# Conn_A.net
KiCad netlist of a schematic drawn in Altium Designer
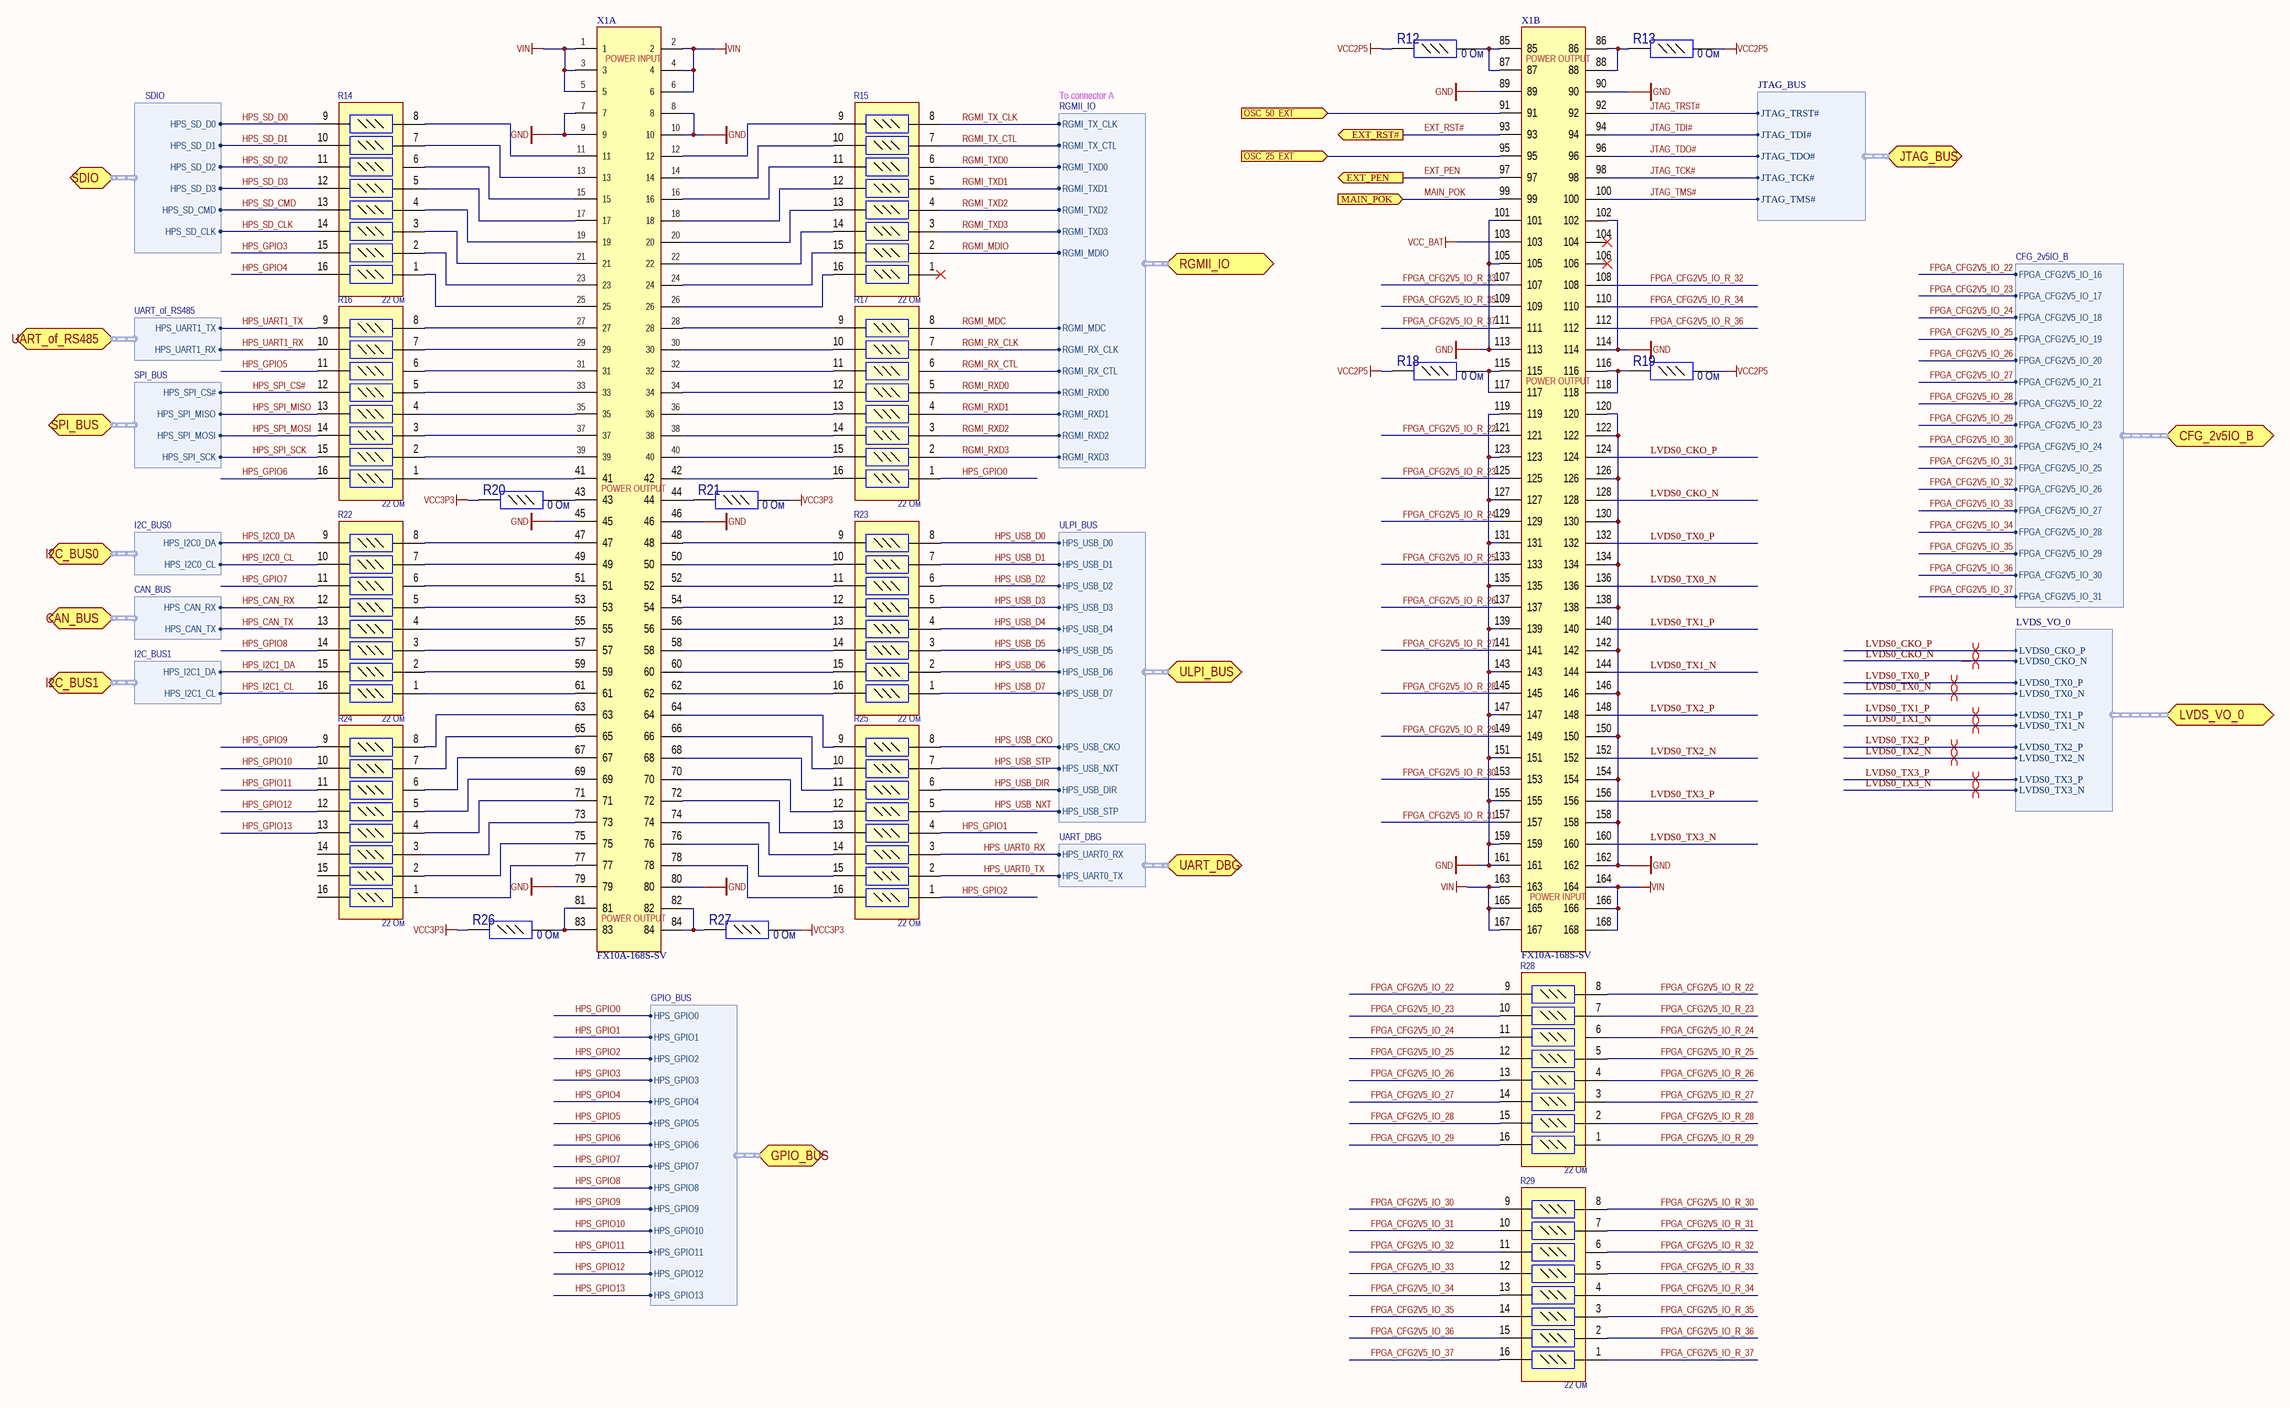
[diagram p0: Conn_A.SchDoc]

(export (version "E")
  (design (tool "Eeschema 10.0.6"))
  (components
    (comp (ref "R12")
      (value "0 Ом")
      (footprint "CR0603")
      (description "Чип резистор")
      (fields (field (name "Comment") "CR0603-0 Ом-±5%"))
      (libsource (lib "Резисторы") (part "CR0603-#-±5%"))
    )
    (comp (ref "R13")
      (value "0 Ом")
      (footprint "CR0603")
      (description "Чип резистор")
      (fields (field (name "Comment") "CR0603-0 Ом-±5%"))
      (libsource (lib "Резисторы") (part "CR0603-#-±5%"))
    )
    (comp (ref "R14")
      (value "22 Ом")
      (footprint "CAT16-J8")
      (description "Набор чип резисторов")
      (fields (field (name "Comment") "YC248-JR-07-22 Ом"))
      (libsource (lib "SD_IC") (part "YC248-JR-07-#"))
    )
    (comp (ref "R15")
      (value "22 Ом")
      (footprint "CAT16-J8")
      (description "Набор чип резисторов")
      (fields (field (name "Comment") "YC248-JR-07-22 Ом"))
      (libsource (lib "SD_IC") (part "YC248-JR-07-#"))
    )
    (comp (ref "R16")
      (value "22 Ом")
      (footprint "CAT16-J8")
      (description "Набор чип резисторов")
      (fields (field (name "Comment") "YC248-JR-07-22 Ом"))
      (libsource (lib "SD_IC") (part "YC248-JR-07-#"))
    )
    (comp (ref "R17")
      (value "22 Ом")
      (footprint "CAT16-J8")
      (description "Набор чип резисторов")
      (fields (field (name "Comment") "YC248-JR-07-22 Ом"))
      (libsource (lib "SD_IC") (part "YC248-JR-07-#"))
    )
    (comp (ref "R18")
      (value "0 Ом")
      (footprint "CR0603")
      (description "Чип резистор")
      (fields (field (name "Comment") "CR0603-0 Ом-±5%"))
      (libsource (lib "Резисторы") (part "CR0603-#-±5%"))
    )
    (comp (ref "R19")
      (value "0 Ом")
      (footprint "CR0603")
      (description "Чип резистор")
      (fields (field (name "Comment") "CR0603-0 Ом-±5%"))
      (libsource (lib "Резисторы") (part "CR0603-#-±5%"))
    )
    (comp (ref "R20")
      (value "0 Ом")
      (footprint "CR0603")
      (description "Чип резистор")
      (fields (field (name "Comment") "CR0603-0 Ом-±5%"))
      (libsource (lib "Резисторы") (part "CR0603-#-±5%"))
    )
    (comp (ref "R21")
      (value "0 Ом")
      (footprint "CR0603")
      (description "Чип резистор")
      (fields (field (name "Comment") "CR0603-0 Ом-±5%"))
      (libsource (lib "Резисторы") (part "CR0603-#-±5%"))
    )
    (comp (ref "R22")
      (value "22 Ом")
      (footprint "CAT16-J8")
      (description "Набор чип резисторов")
      (fields (field (name "Comment") "YC248-JR-07-22 Ом"))
      (libsource (lib "SD_IC") (part "YC248-JR-07-#"))
    )
    (comp (ref "R23")
      (value "22 Ом")
      (footprint "CAT16-J8")
      (description "Набор чип резисторов")
      (fields (field (name "Comment") "YC248-JR-07-22 Ом"))
      (libsource (lib "SD_IC") (part "YC248-JR-07-#"))
    )
    (comp (ref "R24")
      (value "22 Ом")
      (footprint "CAT16-J8")
      (description "Набор чип резисторов")
      (fields (field (name "Comment") "YC248-JR-07-22 Ом"))
      (libsource (lib "SD_IC") (part "YC248-JR-07-#"))
    )
    (comp (ref "R25")
      (value "22 Ом")
      (footprint "CAT16-J8")
      (description "Набор чип резисторов")
      (fields (field (name "Comment") "YC248-JR-07-22 Ом"))
      (libsource (lib "SD_IC") (part "YC248-JR-07-#"))
    )
    (comp (ref "R26")
      (value "0 Ом")
      (footprint "CR0603")
      (description "Чип резистор")
      (fields (field (name "Comment") "CR0603-0 Ом-±5%"))
      (libsource (lib "Резисторы") (part "CR0603-#-±5%"))
    )
    (comp (ref "R27")
      (value "0 Ом")
      (footprint "CR0603")
      (description "Чип резистор")
      (fields (field (name "Comment") "CR0603-0 Ом-±5%"))
      (libsource (lib "Резисторы") (part "CR0603-#-±5%"))
    )
    (comp (ref "R28")
      (value "22 Ом")
      (footprint "CAT16-J8")
      (description "Набор чип резисторов")
      (fields (field (name "Comment") "YC248-JR-07-22 Ом"))
      (libsource (lib "SD_IC") (part "YC248-JR-07-#"))
    )
    (comp (ref "R29")
      (value "22 Ом")
      (footprint "CAT16-J8")
      (description "Набор чип резисторов")
      (fields (field (name "Comment") "YC248-JR-07-22 Ом"))
      (libsource (lib "SD_IC") (part "YC248-JR-07-#"))
    )
    (comp (ref "X1")
      (value "FX10A-168S-SV")
      (footprint "FX10A-168S-SV")
      (libsource (lib "SD_IC") (part "FX10A-168S-SV"))
    )
  )
  (nets
    (net (code "14") (name "/EXT_PEN") (class "Default")
      (node (ref "X1") (pin "97") (pinfunction "97_97") (pintype "passive"))
    )
    (net (code "15") (name "/EXT_RST#") (class "Default")
      (node (ref "X1") (pin "93") (pinfunction "93_93") (pintype "passive"))
    )
    (net (code "16") (name "/FPGA_CFG2V5_IO_22") (class "Default")
      (node (ref "R28") (pin "9") (pintype "passive"))
    )
    (net (code "17") (name "/FPGA_CFG2V5_IO_23") (class "Default")
      (node (ref "R28") (pin "10") (pintype "passive"))
    )
    (net (code "18") (name "/FPGA_CFG2V5_IO_24") (class "Default")
      (node (ref "R28") (pin "11") (pintype "passive"))
    )
    (net (code "19") (name "/FPGA_CFG2V5_IO_25") (class "Default")
      (node (ref "R28") (pin "12") (pintype "passive"))
    )
    (net (code "20") (name "/FPGA_CFG2V5_IO_26") (class "Default")
      (node (ref "R28") (pin "13") (pintype "passive"))
    )
    (net (code "21") (name "/FPGA_CFG2V5_IO_27") (class "Default")
      (node (ref "R28") (pin "14") (pintype "passive"))
    )
    (net (code "22") (name "/FPGA_CFG2V5_IO_28") (class "Default")
      (node (ref "R28") (pin "15") (pintype "passive"))
    )
    (net (code "23") (name "/FPGA_CFG2V5_IO_29") (class "Default")
      (node (ref "R28") (pin "16") (pintype "passive"))
    )
    (net (code "24") (name "/FPGA_CFG2V5_IO_30") (class "Default")
      (node (ref "R29") (pin "9") (pintype "passive"))
    )
    (net (code "25") (name "/FPGA_CFG2V5_IO_31") (class "Default")
      (node (ref "R29") (pin "10") (pintype "passive"))
    )
    (net (code "26") (name "/FPGA_CFG2V5_IO_32") (class "Default")
      (node (ref "R29") (pin "11") (pintype "passive"))
    )
    (net (code "27") (name "/FPGA_CFG2V5_IO_33") (class "Default")
      (node (ref "R29") (pin "12") (pintype "passive"))
    )
    (net (code "28") (name "/FPGA_CFG2V5_IO_34") (class "Default")
      (node (ref "R29") (pin "13") (pintype "passive"))
    )
    (net (code "29") (name "/FPGA_CFG2V5_IO_35") (class "Default")
      (node (ref "R29") (pin "14") (pintype "passive"))
    )
    (net (code "30") (name "/FPGA_CFG2V5_IO_36") (class "Default")
      (node (ref "R29") (pin "15") (pintype "passive"))
    )
    (net (code "31") (name "/FPGA_CFG2V5_IO_37") (class "Default")
      (node (ref "R29") (pin "16") (pintype "passive"))
    )
    (net (code "32") (name "/FPGA_CFG2V5_IO_R_22") (class "Default")
      (node (ref "R28") (pin "8") (pintype "passive"))
      (node (ref "X1") (pin "121") (pinfunction "121_121") (pintype "passive"))
    )
    (net (code "33") (name "/FPGA_CFG2V5_IO_R_23") (class "Default")
      (node (ref "R28") (pin "7") (pintype "passive"))
      (node (ref "X1") (pin "125") (pinfunction "125_125") (pintype "passive"))
    )
    (net (code "34") (name "/FPGA_CFG2V5_IO_R_24") (class "Default")
      (node (ref "R28") (pin "6") (pintype "passive"))
      (node (ref "X1") (pin "129") (pinfunction "129_129") (pintype "passive"))
    )
    (net (code "35") (name "/FPGA_CFG2V5_IO_R_25") (class "Default")
      (node (ref "R28") (pin "5") (pintype "passive"))
      (node (ref "X1") (pin "133") (pinfunction "133_133") (pintype "passive"))
    )
    (net (code "36") (name "/FPGA_CFG2V5_IO_R_26") (class "Default")
      (node (ref "R28") (pin "4") (pintype "passive"))
      (node (ref "X1") (pin "137") (pinfunction "137_137") (pintype "passive"))
    )
    (net (code "37") (name "/FPGA_CFG2V5_IO_R_27") (class "Default")
      (node (ref "R28") (pin "3") (pintype "passive"))
      (node (ref "X1") (pin "141") (pinfunction "141_141") (pintype "passive"))
    )
    (net (code "38") (name "/FPGA_CFG2V5_IO_R_28") (class "Default")
      (node (ref "R28") (pin "2") (pintype "passive"))
      (node (ref "X1") (pin "145") (pinfunction "145_145") (pintype "passive"))
    )
    (net (code "39") (name "/FPGA_CFG2V5_IO_R_29") (class "Default")
      (node (ref "R28") (pin "1") (pintype "passive"))
      (node (ref "X1") (pin "149") (pinfunction "149_149") (pintype "passive"))
    )
    (net (code "40") (name "/FPGA_CFG2V5_IO_R_30") (class "Default")
      (node (ref "R29") (pin "8") (pintype "passive"))
      (node (ref "X1") (pin "153") (pinfunction "153_153") (pintype "passive"))
    )
    (net (code "41") (name "/FPGA_CFG2V5_IO_R_31") (class "Default")
      (node (ref "R29") (pin "7") (pintype "passive"))
      (node (ref "X1") (pin "157") (pinfunction "157_157") (pintype "passive"))
    )
    (net (code "42") (name "/FPGA_CFG2V5_IO_R_32") (class "Default")
      (node (ref "R29") (pin "6") (pintype "passive"))
      (node (ref "X1") (pin "108") (pinfunction "108_108") (pintype "passive"))
    )
    (net (code "43") (name "/FPGA_CFG2V5_IO_R_33") (class "Default")
      (node (ref "R29") (pin "5") (pintype "passive"))
      (node (ref "X1") (pin "107") (pinfunction "107_107") (pintype "passive"))
    )
    (net (code "44") (name "/FPGA_CFG2V5_IO_R_34") (class "Default")
      (node (ref "R29") (pin "4") (pintype "passive"))
      (node (ref "X1") (pin "110") (pinfunction "110_110") (pintype "passive"))
    )
    (net (code "45") (name "/FPGA_CFG2V5_IO_R_35") (class "Default")
      (node (ref "R29") (pin "3") (pintype "passive"))
      (node (ref "X1") (pin "109") (pinfunction "109_109") (pintype "passive"))
    )
    (net (code "46") (name "/FPGA_CFG2V5_IO_R_36") (class "Default")
      (node (ref "R29") (pin "2") (pintype "passive"))
      (node (ref "X1") (pin "112") (pinfunction "112_112") (pintype "passive"))
    )
    (net (code "47") (name "/FPGA_CFG2V5_IO_R_37") (class "Default")
      (node (ref "R29") (pin "1") (pintype "passive"))
      (node (ref "X1") (pin "111") (pinfunction "111_111") (pintype "passive"))
    )
    (net (code "48") (name "/HPS_CAN_RX") (class "Default") (node (ref "R22") (pin "12") (pintype "passive")))
    (net (code "49") (name "/HPS_CAN_TX") (class "Default") (node (ref "R22") (pin "13") (pintype "passive")))
    (net (code "50") (name "/HPS_GPIO0") (class "Default") (node (ref "R17") (pin "1") (pintype "passive")))
    (net (code "51") (name "/HPS_GPIO1") (class "Default") (node (ref "R25") (pin "4") (pintype "passive")))
    (net (code "52") (name "/HPS_GPIO2") (class "Default") (node (ref "R25") (pin "1") (pintype "passive")))
    (net (code "53") (name "/HPS_GPIO3") (class "Default") (node (ref "R14") (pin "15") (pintype "passive")))
    (net (code "54") (name "/HPS_GPIO4") (class "Default") (node (ref "R14") (pin "16") (pintype "passive")))
    (net (code "55") (name "/HPS_GPIO5") (class "Default") (node (ref "R16") (pin "11") (pintype "passive")))
    (net (code "56") (name "/HPS_GPIO6") (class "Default") (node (ref "R16") (pin "16") (pintype "passive")))
    (net (code "57") (name "/HPS_GPIO7") (class "Default") (node (ref "R22") (pin "11") (pintype "passive")))
    (net (code "58") (name "/HPS_GPIO8") (class "Default") (node (ref "R22") (pin "14") (pintype "passive")))
    (net (code "59") (name "/HPS_GPIO9") (class "Default") (node (ref "R24") (pin "9") (pintype "passive")))
    (net (code "60") (name "/HPS_GPIO10") (class "Default") (node (ref "R24") (pin "10") (pintype "passive")))
    (net (code "61") (name "/HPS_GPIO11") (class "Default") (node (ref "R24") (pin "11") (pintype "passive")))
    (net (code "62") (name "/HPS_GPIO12") (class "Default") (node (ref "R24") (pin "12") (pintype "passive")))
    (net (code "63") (name "/HPS_GPIO13") (class "Default") (node (ref "R24") (pin "13") (pintype "passive")))
    (net (code "64") (name "/HPS_I2C0_CL") (class "Default")
      (node (ref "R22") (pin "10") (pintype "passive"))
    )
    (net (code "65") (name "/HPS_I2C0_DA") (class "Default") (node (ref "R22") (pin "9") (pintype "passive")))
    (net (code "66") (name "/HPS_I2C1_CL") (class "Default")
      (node (ref "R22") (pin "16") (pintype "passive"))
    )
    (net (code "67") (name "/HPS_I2C1_DA") (class "Default")
      (node (ref "R22") (pin "15") (pintype "passive"))
    )
    (net (code "68") (name "/HPS_SD_CLK") (class "Default") (node (ref "R14") (pin "14") (pintype "passive")))
    (net (code "69") (name "/HPS_SD_CMD") (class "Default") (node (ref "R14") (pin "13") (pintype "passive")))
    (net (code "70") (name "/HPS_SD_D0") (class "Default") (node (ref "R14") (pin "9") (pintype "passive")))
    (net (code "71") (name "/HPS_SD_D1") (class "Default") (node (ref "R14") (pin "10") (pintype "passive")))
    (net (code "72") (name "/HPS_SD_D2") (class "Default") (node (ref "R14") (pin "11") (pintype "passive")))
    (net (code "73") (name "/HPS_SD_D3") (class "Default") (node (ref "R14") (pin "12") (pintype "passive")))
    (net (code "74") (name "/HPS_SPI_CS#") (class "Default")
      (node (ref "R16") (pin "12") (pintype "passive"))
    )
    (net (code "75") (name "/HPS_SPI_MISO") (class "Default")
      (node (ref "R16") (pin "13") (pintype "passive"))
    )
    (net (code "76") (name "/HPS_SPI_MOSI") (class "Default")
      (node (ref "R16") (pin "14") (pintype "passive"))
    )
    (net (code "77") (name "/HPS_SPI_SCK") (class "Default")
      (node (ref "R16") (pin "15") (pintype "passive"))
    )
    (net (code "78") (name "/HPS_UART0_RX") (class "Default")
      (node (ref "R25") (pin "3") (pintype "passive"))
    )
    (net (code "79") (name "/HPS_UART0_TX") (class "Default")
      (node (ref "R25") (pin "2") (pintype "passive"))
    )
    (net (code "80") (name "/HPS_UART1_RX") (class "Default")
      (node (ref "R16") (pin "10") (pintype "passive"))
    )
    (net (code "81") (name "/HPS_UART1_TX") (class "Default")
      (node (ref "R16") (pin "9") (pintype "passive"))
    )
    (net (code "82") (name "/HPS_USB_CKO") (class "Default") (node (ref "R25") (pin "8") (pintype "passive")))
    (net (code "83") (name "/HPS_USB_D0") (class "Default") (node (ref "R23") (pin "8") (pintype "passive")))
    (net (code "84") (name "/HPS_USB_D1") (class "Default") (node (ref "R23") (pin "7") (pintype "passive")))
    (net (code "85") (name "/HPS_USB_D2") (class "Default") (node (ref "R23") (pin "6") (pintype "passive")))
    (net (code "86") (name "/HPS_USB_D3") (class "Default") (node (ref "R23") (pin "5") (pintype "passive")))
    (net (code "87") (name "/HPS_USB_D4") (class "Default") (node (ref "R23") (pin "4") (pintype "passive")))
    (net (code "88") (name "/HPS_USB_D5") (class "Default") (node (ref "R23") (pin "3") (pintype "passive")))
    (net (code "89") (name "/HPS_USB_D6") (class "Default") (node (ref "R23") (pin "2") (pintype "passive")))
    (net (code "90") (name "/HPS_USB_D7") (class "Default") (node (ref "R23") (pin "1") (pintype "passive")))
    (net (code "91") (name "/HPS_USB_DIR") (class "Default") (node (ref "R25") (pin "6") (pintype "passive")))
    (net (code "92") (name "/HPS_USB_NXT") (class "Default") (node (ref "R25") (pin "5") (pintype "passive")))
    (net (code "93") (name "/HPS_USB_STP") (class "Default") (node (ref "R25") (pin "7") (pintype "passive")))
    (net (code "94") (name "/JTAG_TCK#") (class "Default")
      (node (ref "X1") (pin "98") (pinfunction "98_98") (pintype "passive"))
    )
    (net (code "95") (name "/JTAG_TDI#") (class "Default")
      (node (ref "X1") (pin "94") (pinfunction "94_94") (pintype "passive"))
    )
    (net (code "96") (name "/JTAG_TDO#") (class "Default")
      (node (ref "X1") (pin "96") (pinfunction "96_96") (pintype "passive"))
    )
    (net (code "97") (name "/JTAG_TMS#") (class "Default")
      (node (ref "X1") (pin "100") (pinfunction "100_100") (pintype "passive"))
    )
    (net (code "98") (name "/JTAG_TRST#") (class "Default")
      (node (ref "X1") (pin "92") (pinfunction "92_92") (pintype "passive"))
    )
    (net (code "99") (name "/LVDS0_CKO_N") (class "Default")
      (node (ref "X1") (pin "128") (pinfunction "128_128") (pintype "passive"))
    )
    (net (code "100") (name "/LVDS0_CKO_P") (class "Default")
      (node (ref "X1") (pin "124") (pinfunction "124_124") (pintype "passive"))
    )
    (net (code "101") (name "/LVDS0_TX0_N") (class "Default")
      (node (ref "X1") (pin "136") (pinfunction "136_136") (pintype "passive"))
    )
    (net (code "102") (name "/LVDS0_TX0_P") (class "Default")
      (node (ref "X1") (pin "132") (pinfunction "132_132") (pintype "passive"))
    )
    (net (code "103") (name "/LVDS0_TX1_N") (class "Default")
      (node (ref "X1") (pin "144") (pinfunction "144_144") (pintype "passive"))
    )
    (net (code "104") (name "/LVDS0_TX1_P") (class "Default")
      (node (ref "X1") (pin "140") (pinfunction "140_140") (pintype "passive"))
    )
    (net (code "105") (name "/LVDS0_TX2_N") (class "Default")
      (node (ref "X1") (pin "152") (pinfunction "152_152") (pintype "passive"))
    )
    (net (code "106") (name "/LVDS0_TX2_P") (class "Default")
      (node (ref "X1") (pin "148") (pinfunction "148_148") (pintype "passive"))
    )
    (net (code "107") (name "/LVDS0_TX3_N") (class "Default")
      (node (ref "X1") (pin "160") (pinfunction "160_160") (pintype "passive"))
    )
    (net (code "108") (name "/LVDS0_TX3_P") (class "Default")
      (node (ref "X1") (pin "156") (pinfunction "156_156") (pintype "passive"))
    )
    (net (code "109") (name "/MAIN_POK") (class "Default")
      (node (ref "X1") (pin "99") (pinfunction "99_99") (pintype "passive"))
    )
    (net (code "110") (name "/OSC_25_EXT") (class "Default")
      (node (ref "X1") (pin "95") (pinfunction "95_95") (pintype "passive"))
    )
    (net (code "111") (name "/OSC_50_EXT") (class "Default")
      (node (ref "X1") (pin "91") (pinfunction "91_91") (pintype "passive"))
    )
    (net (code "112") (name "/RGMI_MDC") (class "Default") (node (ref "R17") (pin "8") (pintype "passive")))
    (net (code "113") (name "/RGMI_MDIO") (class "Default") (node (ref "R15") (pin "2") (pintype "passive")))
    (net (code "114") (name "/RGMI_RXD0") (class "Default") (node (ref "R17") (pin "5") (pintype "passive")))
    (net (code "115") (name "/RGMI_RXD1") (class "Default") (node (ref "R17") (pin "4") (pintype "passive")))
    (net (code "116") (name "/RGMI_RXD2") (class "Default") (node (ref "R17") (pin "3") (pintype "passive")))
    (net (code "117") (name "/RGMI_RXD3") (class "Default") (node (ref "R17") (pin "2") (pintype "passive")))
    (net (code "118") (name "/RGMI_RX_CLK") (class "Default")
      (node (ref "R17") (pin "7") (pintype "passive"))
    )
    (net (code "119") (name "/RGMI_RX_CTL") (class "Default")
      (node (ref "R17") (pin "6") (pintype "passive"))
    )
    (net (code "120") (name "/RGMI_TXD0") (class "Default") (node (ref "R15") (pin "6") (pintype "passive")))
    (net (code "121") (name "/RGMI_TXD1") (class "Default") (node (ref "R15") (pin "5") (pintype "passive")))
    (net (code "122") (name "/RGMI_TXD2") (class "Default") (node (ref "R15") (pin "4") (pintype "passive")))
    (net (code "123") (name "/RGMI_TXD3") (class "Default") (node (ref "R15") (pin "3") (pintype "passive")))
    (net (code "124") (name "/RGMI_TX_CLK") (class "Default")
      (node (ref "R15") (pin "8") (pintype "passive"))
    )
    (net (code "125") (name "/RGMI_TX_CTL") (class "Default")
      (node (ref "R15") (pin "7") (pintype "passive"))
    )
    (net (code "139") (name "GND") (class "Default")
      (node (ref "X1") (pin "10") (pinfunction "10_10") (pintype "passive"))
      (node (ref "X1") (pin "101") (pinfunction "101_101") (pintype "passive"))
      (node (ref "X1") (pin "102") (pinfunction "102_102") (pintype "passive"))
      (node (ref "X1") (pin "105") (pinfunction "105_105") (pintype "passive"))
      (node (ref "X1") (pin "113") (pinfunction "113_113") (pintype "passive"))
      (node (ref "X1") (pin "114") (pinfunction "114_114") (pintype "passive"))
      (node (ref "X1") (pin "119") (pinfunction "119_119") (pintype "passive"))
      (node (ref "X1") (pin "120") (pinfunction "120_120") (pintype "passive"))
      (node (ref "X1") (pin "122") (pinfunction "122_122") (pintype "passive"))
      (node (ref "X1") (pin "123") (pinfunction "123_123") (pintype "passive"))
      (node (ref "X1") (pin "126") (pinfunction "126_126") (pintype "passive"))
      (node (ref "X1") (pin "127") (pinfunction "127_127") (pintype "passive"))
      (node (ref "X1") (pin "130") (pinfunction "130_130") (pintype "passive"))
      (node (ref "X1") (pin "131") (pinfunction "131_131") (pintype "passive"))
      (node (ref "X1") (pin "134") (pinfunction "134_134") (pintype "passive"))
      (node (ref "X1") (pin "135") (pinfunction "135_135") (pintype "passive"))
      (node (ref "X1") (pin "138") (pinfunction "138_138") (pintype "passive"))
      (node (ref "X1") (pin "139") (pinfunction "139_139") (pintype "passive"))
      (node (ref "X1") (pin "142") (pinfunction "142_142") (pintype "passive"))
      (node (ref "X1") (pin "143") (pinfunction "143_143") (pintype "passive"))
      (node (ref "X1") (pin "146") (pinfunction "146_146") (pintype "passive"))
      (node (ref "X1") (pin "147") (pinfunction "147_147") (pintype "passive"))
      (node (ref "X1") (pin "150") (pinfunction "150_150") (pintype "passive"))
      (node (ref "X1") (pin "151") (pinfunction "151_151") (pintype "passive"))
      (node (ref "X1") (pin "154") (pinfunction "154_154") (pintype "passive"))
      (node (ref "X1") (pin "155") (pinfunction "155_155") (pintype "passive"))
      (node (ref "X1") (pin "158") (pinfunction "158_158") (pintype "passive"))
      (node (ref "X1") (pin "159") (pinfunction "159_159") (pintype "passive"))
      (node (ref "X1") (pin "161") (pinfunction "161_161") (pintype "passive"))
      (node (ref "X1") (pin "162") (pinfunction "162_162") (pintype "passive"))
      (node (ref "X1") (pin "45") (pinfunction "45_45") (pintype "passive"))
      (node (ref "X1") (pin "46") (pinfunction "46_46") (pintype "passive"))
      (node (ref "X1") (pin "7") (pinfunction "7_7") (pintype "passive"))
      (node (ref "X1") (pin "79") (pinfunction "79_79") (pintype "passive"))
      (node (ref "X1") (pin "8") (pinfunction "8_8") (pintype "passive"))
      (node (ref "X1") (pin "80") (pinfunction "80_80") (pintype "passive"))
      (node (ref "X1") (pin "89") (pinfunction "89_89") (pintype "passive"))
      (node (ref "X1") (pin "9") (pinfunction "9_9") (pintype "passive"))
      (node (ref "X1") (pin "90") (pinfunction "90_90") (pintype "passive"))
    )
    (net (code "140") (name "Net-(R12--)") (class "Default")
      (node (ref "R12") (pin "2") (pinfunction "-_2") (pintype "passive"))
      (node (ref "X1") (pin "85") (pinfunction "85_85") (pintype "passive"))
      (node (ref "X1") (pin "87") (pinfunction "87_87") (pintype "passive"))
    )
    (net (code "141") (name "Net-(R13-+)") (class "Default")
      (node (ref "R13") (pin "1") (pinfunction "+_1") (pintype "passive"))
      (node (ref "X1") (pin "86") (pinfunction "86_86") (pintype "passive"))
      (node (ref "X1") (pin "88") (pinfunction "88_88") (pintype "passive"))
    )
    (net (code "142") (name "Net-(R14-Pad1)") (class "Default")
      (node (ref "R14") (pin "1") (pintype "passive"))
      (node (ref "X1") (pin "25") (pinfunction "25_25") (pintype "passive"))
    )
    (net (code "143") (name "Net-(R14-Pad2)") (class "Default")
      (node (ref "R14") (pin "2") (pintype "passive"))
      (node (ref "X1") (pin "23") (pinfunction "23_23") (pintype "passive"))
    )
    (net (code "144") (name "Net-(R14-Pad3)") (class "Default")
      (node (ref "R14") (pin "3") (pintype "passive"))
      (node (ref "X1") (pin "21") (pinfunction "21_21") (pintype "passive"))
    )
    (net (code "145") (name "Net-(R14-Pad4)") (class "Default")
      (node (ref "R14") (pin "4") (pintype "passive"))
      (node (ref "X1") (pin "19") (pinfunction "19_19") (pintype "passive"))
    )
    (net (code "146") (name "Net-(R14-Pad5)") (class "Default")
      (node (ref "R14") (pin "5") (pintype "passive"))
      (node (ref "X1") (pin "17") (pinfunction "17_17") (pintype "passive"))
    )
    (net (code "147") (name "Net-(R14-Pad6)") (class "Default")
      (node (ref "R14") (pin "6") (pintype "passive"))
      (node (ref "X1") (pin "15") (pinfunction "15_15") (pintype "passive"))
    )
    (net (code "148") (name "Net-(R14-Pad7)") (class "Default")
      (node (ref "R14") (pin "7") (pintype "passive"))
      (node (ref "X1") (pin "13") (pinfunction "13_13") (pintype "passive"))
    )
    (net (code "149") (name "Net-(R14-Pad8)") (class "Default")
      (node (ref "R14") (pin "8") (pintype "passive"))
      (node (ref "X1") (pin "11") (pinfunction "11_11") (pintype "passive"))
    )
    (net (code "150") (name "Net-(R15-Pad9)") (class "Default")
      (node (ref "R15") (pin "9") (pintype "passive"))
      (node (ref "X1") (pin "12") (pinfunction "12_12") (pintype "passive"))
    )
    (net (code "151") (name "Net-(R15-Pad10)") (class "Default")
      (node (ref "R15") (pin "10") (pintype "passive"))
      (node (ref "X1") (pin "14") (pinfunction "14_14") (pintype "passive"))
    )
    (net (code "152") (name "Net-(R15-Pad11)") (class "Default")
      (node (ref "R15") (pin "11") (pintype "passive"))
      (node (ref "X1") (pin "16") (pinfunction "16_16") (pintype "passive"))
    )
    (net (code "153") (name "Net-(R15-Pad12)") (class "Default")
      (node (ref "R15") (pin "12") (pintype "passive"))
      (node (ref "X1") (pin "18") (pinfunction "18_18") (pintype "passive"))
    )
    (net (code "154") (name "Net-(R15-Pad13)") (class "Default")
      (node (ref "R15") (pin "13") (pintype "passive"))
      (node (ref "X1") (pin "20") (pinfunction "20_20") (pintype "passive"))
    )
    (net (code "155") (name "Net-(R15-Pad14)") (class "Default")
      (node (ref "R15") (pin "14") (pintype "passive"))
      (node (ref "X1") (pin "22") (pinfunction "22_22") (pintype "passive"))
    )
    (net (code "156") (name "Net-(R15-Pad15)") (class "Default")
      (node (ref "R15") (pin "15") (pintype "passive"))
      (node (ref "X1") (pin "24") (pinfunction "24_24") (pintype "passive"))
    )
    (net (code "157") (name "Net-(R15-Pad16)") (class "Default")
      (node (ref "R15") (pin "16") (pintype "passive"))
      (node (ref "X1") (pin "26") (pinfunction "26_26") (pintype "passive"))
    )
    (net (code "158") (name "Net-(R16-Pad1)") (class "Default")
      (node (ref "R16") (pin "1") (pintype "passive"))
      (node (ref "X1") (pin "41") (pinfunction "41_41") (pintype "passive"))
    )
    (net (code "159") (name "Net-(R16-Pad2)") (class "Default")
      (node (ref "R16") (pin "2") (pintype "passive"))
      (node (ref "X1") (pin "39") (pinfunction "39_39") (pintype "passive"))
    )
    (net (code "160") (name "Net-(R16-Pad3)") (class "Default")
      (node (ref "R16") (pin "3") (pintype "passive"))
      (node (ref "X1") (pin "37") (pinfunction "37_37") (pintype "passive"))
    )
    (net (code "161") (name "Net-(R16-Pad4)") (class "Default")
      (node (ref "R16") (pin "4") (pintype "passive"))
      (node (ref "X1") (pin "35") (pinfunction "35_35") (pintype "passive"))
    )
    (net (code "162") (name "Net-(R16-Pad5)") (class "Default")
      (node (ref "R16") (pin "5") (pintype "passive"))
      (node (ref "X1") (pin "33") (pinfunction "33_33") (pintype "passive"))
    )
    (net (code "163") (name "Net-(R16-Pad6)") (class "Default")
      (node (ref "R16") (pin "6") (pintype "passive"))
      (node (ref "X1") (pin "31") (pinfunction "31_31") (pintype "passive"))
    )
    (net (code "164") (name "Net-(R16-Pad7)") (class "Default")
      (node (ref "R16") (pin "7") (pintype "passive"))
      (node (ref "X1") (pin "29") (pinfunction "29_29") (pintype "passive"))
    )
    (net (code "165") (name "Net-(R16-Pad8)") (class "Default")
      (node (ref "R16") (pin "8") (pintype "passive"))
      (node (ref "X1") (pin "27") (pinfunction "27_27") (pintype "passive"))
    )
    (net (code "166") (name "Net-(R17-Pad9)") (class "Default")
      (node (ref "R17") (pin "9") (pintype "passive"))
      (node (ref "X1") (pin "28") (pinfunction "28_28") (pintype "passive"))
    )
    (net (code "167") (name "Net-(R17-Pad10)") (class "Default")
      (node (ref "R17") (pin "10") (pintype "passive"))
      (node (ref "X1") (pin "30") (pinfunction "30_30") (pintype "passive"))
    )
    (net (code "168") (name "Net-(R17-Pad11)") (class "Default")
      (node (ref "R17") (pin "11") (pintype "passive"))
      (node (ref "X1") (pin "32") (pinfunction "32_32") (pintype "passive"))
    )
    (net (code "169") (name "Net-(R17-Pad12)") (class "Default")
      (node (ref "R17") (pin "12") (pintype "passive"))
      (node (ref "X1") (pin "34") (pinfunction "34_34") (pintype "passive"))
    )
    (net (code "170") (name "Net-(R17-Pad13)") (class "Default")
      (node (ref "R17") (pin "13") (pintype "passive"))
      (node (ref "X1") (pin "36") (pinfunction "36_36") (pintype "passive"))
    )
    (net (code "171") (name "Net-(R17-Pad14)") (class "Default")
      (node (ref "R17") (pin "14") (pintype "passive"))
      (node (ref "X1") (pin "38") (pinfunction "38_38") (pintype "passive"))
    )
    (net (code "172") (name "Net-(R17-Pad15)") (class "Default")
      (node (ref "R17") (pin "15") (pintype "passive"))
      (node (ref "X1") (pin "40") (pinfunction "40_40") (pintype "passive"))
    )
    (net (code "173") (name "Net-(R17-Pad16)") (class "Default")
      (node (ref "R17") (pin "16") (pintype "passive"))
      (node (ref "X1") (pin "42") (pinfunction "42_42") (pintype "passive"))
    )
    (net (code "174") (name "Net-(R18--)") (class "Default")
      (node (ref "R18") (pin "2") (pinfunction "-_2") (pintype "passive"))
      (node (ref "X1") (pin "115") (pinfunction "115_115") (pintype "passive"))
      (node (ref "X1") (pin "117") (pinfunction "117_117") (pintype "passive"))
    )
    (net (code "175") (name "Net-(R19-+)") (class "Default")
      (node (ref "R19") (pin "1") (pinfunction "+_1") (pintype "passive"))
      (node (ref "X1") (pin "116") (pinfunction "116_116") (pintype "passive"))
      (node (ref "X1") (pin "118") (pinfunction "118_118") (pintype "passive"))
    )
    (net (code "176") (name "Net-(R20--)") (class "Default")
      (node (ref "R20") (pin "2") (pinfunction "-_2") (pintype "passive"))
      (node (ref "X1") (pin "43") (pinfunction "43_43") (pintype "passive"))
    )
    (net (code "177") (name "Net-(R21-+)") (class "Default")
      (node (ref "R21") (pin "1") (pinfunction "+_1") (pintype "passive"))
      (node (ref "X1") (pin "44") (pinfunction "44_44") (pintype "passive"))
    )
    (net (code "178") (name "Net-(R22-Pad1)") (class "Default")
      (node (ref "R22") (pin "1") (pintype "passive"))
      (node (ref "X1") (pin "61") (pinfunction "61_61") (pintype "passive"))
    )
    (net (code "179") (name "Net-(R22-Pad2)") (class "Default")
      (node (ref "R22") (pin "2") (pintype "passive"))
      (node (ref "X1") (pin "59") (pinfunction "59_59") (pintype "passive"))
    )
    (net (code "180") (name "Net-(R22-Pad3)") (class "Default")
      (node (ref "R22") (pin "3") (pintype "passive"))
      (node (ref "X1") (pin "57") (pinfunction "57_57") (pintype "passive"))
    )
    (net (code "181") (name "Net-(R22-Pad4)") (class "Default")
      (node (ref "R22") (pin "4") (pintype "passive"))
      (node (ref "X1") (pin "55") (pinfunction "55_55") (pintype "passive"))
    )
    (net (code "182") (name "Net-(R22-Pad5)") (class "Default")
      (node (ref "R22") (pin "5") (pintype "passive"))
      (node (ref "X1") (pin "53") (pinfunction "53_53") (pintype "passive"))
    )
    (net (code "183") (name "Net-(R22-Pad6)") (class "Default")
      (node (ref "R22") (pin "6") (pintype "passive"))
      (node (ref "X1") (pin "51") (pinfunction "51_51") (pintype "passive"))
    )
    (net (code "184") (name "Net-(R22-Pad7)") (class "Default")
      (node (ref "R22") (pin "7") (pintype "passive"))
      (node (ref "X1") (pin "49") (pinfunction "49_49") (pintype "passive"))
    )
    (net (code "185") (name "Net-(R22-Pad8)") (class "Default")
      (node (ref "R22") (pin "8") (pintype "passive"))
      (node (ref "X1") (pin "47") (pinfunction "47_47") (pintype "passive"))
    )
    (net (code "186") (name "Net-(R23-Pad9)") (class "Default")
      (node (ref "R23") (pin "9") (pintype "passive"))
      (node (ref "X1") (pin "48") (pinfunction "48_48") (pintype "passive"))
    )
    (net (code "187") (name "Net-(R23-Pad10)") (class "Default")
      (node (ref "R23") (pin "10") (pintype "passive"))
      (node (ref "X1") (pin "50") (pinfunction "50_50") (pintype "passive"))
    )
    (net (code "188") (name "Net-(R23-Pad11)") (class "Default")
      (node (ref "R23") (pin "11") (pintype "passive"))
      (node (ref "X1") (pin "52") (pinfunction "52_52") (pintype "passive"))
    )
    (net (code "189") (name "Net-(R23-Pad12)") (class "Default")
      (node (ref "R23") (pin "12") (pintype "passive"))
      (node (ref "X1") (pin "54") (pinfunction "54_54") (pintype "passive"))
    )
    (net (code "190") (name "Net-(R23-Pad13)") (class "Default")
      (node (ref "R23") (pin "13") (pintype "passive"))
      (node (ref "X1") (pin "56") (pinfunction "56_56") (pintype "passive"))
    )
    (net (code "191") (name "Net-(R23-Pad14)") (class "Default")
      (node (ref "R23") (pin "14") (pintype "passive"))
      (node (ref "X1") (pin "58") (pinfunction "58_58") (pintype "passive"))
    )
    (net (code "192") (name "Net-(R23-Pad15)") (class "Default")
      (node (ref "R23") (pin "15") (pintype "passive"))
      (node (ref "X1") (pin "60") (pinfunction "60_60") (pintype "passive"))
    )
    (net (code "193") (name "Net-(R23-Pad16)") (class "Default")
      (node (ref "R23") (pin "16") (pintype "passive"))
      (node (ref "X1") (pin "62") (pinfunction "62_62") (pintype "passive"))
    )
    (net (code "194") (name "Net-(R24-Pad1)") (class "Default")
      (node (ref "R24") (pin "1") (pintype "passive"))
      (node (ref "X1") (pin "77") (pinfunction "77_77") (pintype "passive"))
    )
    (net (code "195") (name "Net-(R24-Pad2)") (class "Default")
      (node (ref "R24") (pin "2") (pintype "passive"))
      (node (ref "X1") (pin "75") (pinfunction "75_75") (pintype "passive"))
    )
    (net (code "196") (name "Net-(R24-Pad3)") (class "Default")
      (node (ref "R24") (pin "3") (pintype "passive"))
      (node (ref "X1") (pin "73") (pinfunction "73_73") (pintype "passive"))
    )
    (net (code "197") (name "Net-(R24-Pad4)") (class "Default")
      (node (ref "R24") (pin "4") (pintype "passive"))
      (node (ref "X1") (pin "71") (pinfunction "71_71") (pintype "passive"))
    )
    (net (code "198") (name "Net-(R24-Pad5)") (class "Default")
      (node (ref "R24") (pin "5") (pintype "passive"))
      (node (ref "X1") (pin "69") (pinfunction "69_69") (pintype "passive"))
    )
    (net (code "199") (name "Net-(R24-Pad6)") (class "Default")
      (node (ref "R24") (pin "6") (pintype "passive"))
      (node (ref "X1") (pin "67") (pinfunction "67_67") (pintype "passive"))
    )
    (net (code "200") (name "Net-(R24-Pad7)") (class "Default")
      (node (ref "R24") (pin "7") (pintype "passive"))
      (node (ref "X1") (pin "65") (pinfunction "65_65") (pintype "passive"))
    )
    (net (code "201") (name "Net-(R24-Pad8)") (class "Default")
      (node (ref "R24") (pin "8") (pintype "passive"))
      (node (ref "X1") (pin "63") (pinfunction "63_63") (pintype "passive"))
    )
    (net (code "202") (name "Net-(R25-Pad9)") (class "Default")
      (node (ref "R25") (pin "9") (pintype "passive"))
      (node (ref "X1") (pin "64") (pinfunction "64_64") (pintype "passive"))
    )
    (net (code "203") (name "Net-(R25-Pad10)") (class "Default")
      (node (ref "R25") (pin "10") (pintype "passive"))
      (node (ref "X1") (pin "66") (pinfunction "66_66") (pintype "passive"))
    )
    (net (code "204") (name "Net-(R25-Pad11)") (class "Default")
      (node (ref "R25") (pin "11") (pintype "passive"))
      (node (ref "X1") (pin "68") (pinfunction "68_68") (pintype "passive"))
    )
    (net (code "205") (name "Net-(R25-Pad12)") (class "Default")
      (node (ref "R25") (pin "12") (pintype "passive"))
      (node (ref "X1") (pin "70") (pinfunction "70_70") (pintype "passive"))
    )
    (net (code "206") (name "Net-(R25-Pad13)") (class "Default")
      (node (ref "R25") (pin "13") (pintype "passive"))
      (node (ref "X1") (pin "72") (pinfunction "72_72") (pintype "passive"))
    )
    (net (code "207") (name "Net-(R25-Pad14)") (class "Default")
      (node (ref "R25") (pin "14") (pintype "passive"))
      (node (ref "X1") (pin "74") (pinfunction "74_74") (pintype "passive"))
    )
    (net (code "208") (name "Net-(R25-Pad15)") (class "Default")
      (node (ref "R25") (pin "15") (pintype "passive"))
      (node (ref "X1") (pin "76") (pinfunction "76_76") (pintype "passive"))
    )
    (net (code "209") (name "Net-(R25-Pad16)") (class "Default")
      (node (ref "R25") (pin "16") (pintype "passive"))
      (node (ref "X1") (pin "78") (pinfunction "78_78") (pintype "passive"))
    )
    (net (code "210") (name "Net-(R26--)") (class "Default")
      (node (ref "R26") (pin "2") (pinfunction "-_2") (pintype "passive"))
      (node (ref "X1") (pin "81") (pinfunction "81_81") (pintype "passive"))
      (node (ref "X1") (pin "83") (pinfunction "83_83") (pintype "passive"))
    )
    (net (code "211") (name "Net-(R27-+)") (class "Default")
      (node (ref "R27") (pin "1") (pinfunction "+_1") (pintype "passive"))
      (node (ref "X1") (pin "82") (pinfunction "82_82") (pintype "passive"))
      (node (ref "X1") (pin "84") (pinfunction "84_84") (pintype "passive"))
    )
    (net (code "212") (name "VCC2P5") (class "Default")
      (node (ref "R12") (pin "1") (pinfunction "+_1") (pintype "passive"))
      (node (ref "R13") (pin "2") (pinfunction "-_2") (pintype "passive"))
      (node (ref "R18") (pin "1") (pinfunction "+_1") (pintype "passive"))
      (node (ref "R19") (pin "2") (pinfunction "-_2") (pintype "passive"))
    )
    (net (code "213") (name "VCC3P3") (class "Default")
      (node (ref "R20") (pin "1") (pinfunction "+_1") (pintype "passive"))
      (node (ref "R21") (pin "2") (pinfunction "-_2") (pintype "passive"))
      (node (ref "R26") (pin "1") (pinfunction "+_1") (pintype "passive"))
      (node (ref "R27") (pin "2") (pinfunction "-_2") (pintype "passive"))
    )
    (net (code "214") (name "VCC_BAT") (class "Default")
      (node (ref "X1") (pin "103") (pinfunction "103_103") (pintype "passive"))
    )
    (net (code "215") (name "VIN") (class "Default")
      (node (ref "X1") (pin "1") (pinfunction "1_1") (pintype "passive"))
      (node (ref "X1") (pin "163") (pinfunction "163_163") (pintype "passive"))
      (node (ref "X1") (pin "164") (pinfunction "164_164") (pintype "passive"))
      (node (ref "X1") (pin "165") (pinfunction "165_165") (pintype "passive"))
      (node (ref "X1") (pin "166") (pinfunction "166_166") (pintype "passive"))
      (node (ref "X1") (pin "167") (pinfunction "167_167") (pintype "passive"))
      (node (ref "X1") (pin "168") (pinfunction "168_168") (pintype "passive"))
      (node (ref "X1") (pin "2") (pinfunction "2_2") (pintype "passive"))
      (node (ref "X1") (pin "3") (pinfunction "3_3") (pintype "passive"))
      (node (ref "X1") (pin "4") (pinfunction "4_4") (pintype "passive"))
      (node (ref "X1") (pin "5") (pinfunction "5_5") (pintype "passive"))
      (node (ref "X1") (pin "6") (pinfunction "6_6") (pintype "passive"))
    )
    (net (code "216") (name "unconnected-(R15-Pad1)") (class "Default")
      (node (ref "R15") (pin "1") (pintype "passive+no_connect"))
    )
    (net (code "217") (name "unconnected-(R24-Pad14)") (class "Default")
      (node (ref "R24") (pin "14") (pintype "passive"))
    )
    (net (code "218") (name "unconnected-(R24-Pad15)") (class "Default")
      (node (ref "R24") (pin "15") (pintype "passive"))
    )
    (net (code "219") (name "unconnected-(R24-Pad16)") (class "Default")
      (node (ref "R24") (pin "16") (pintype "passive"))
    )
    (net (code "220") (name "unconnected-(X1-Pad104)") (class "Default")
      (node (ref "X1") (pin "104") (pinfunction "104_104") (pintype "passive+no_connect"))
    )
    (net (code "221") (name "unconnected-(X1-Pad106)") (class "Default")
      (node (ref "X1") (pin "106") (pinfunction "106_106") (pintype "passive+no_connect"))
    )
  )
)
